# top.net
KiCad netlist of a schematic drawn in Altium Designer
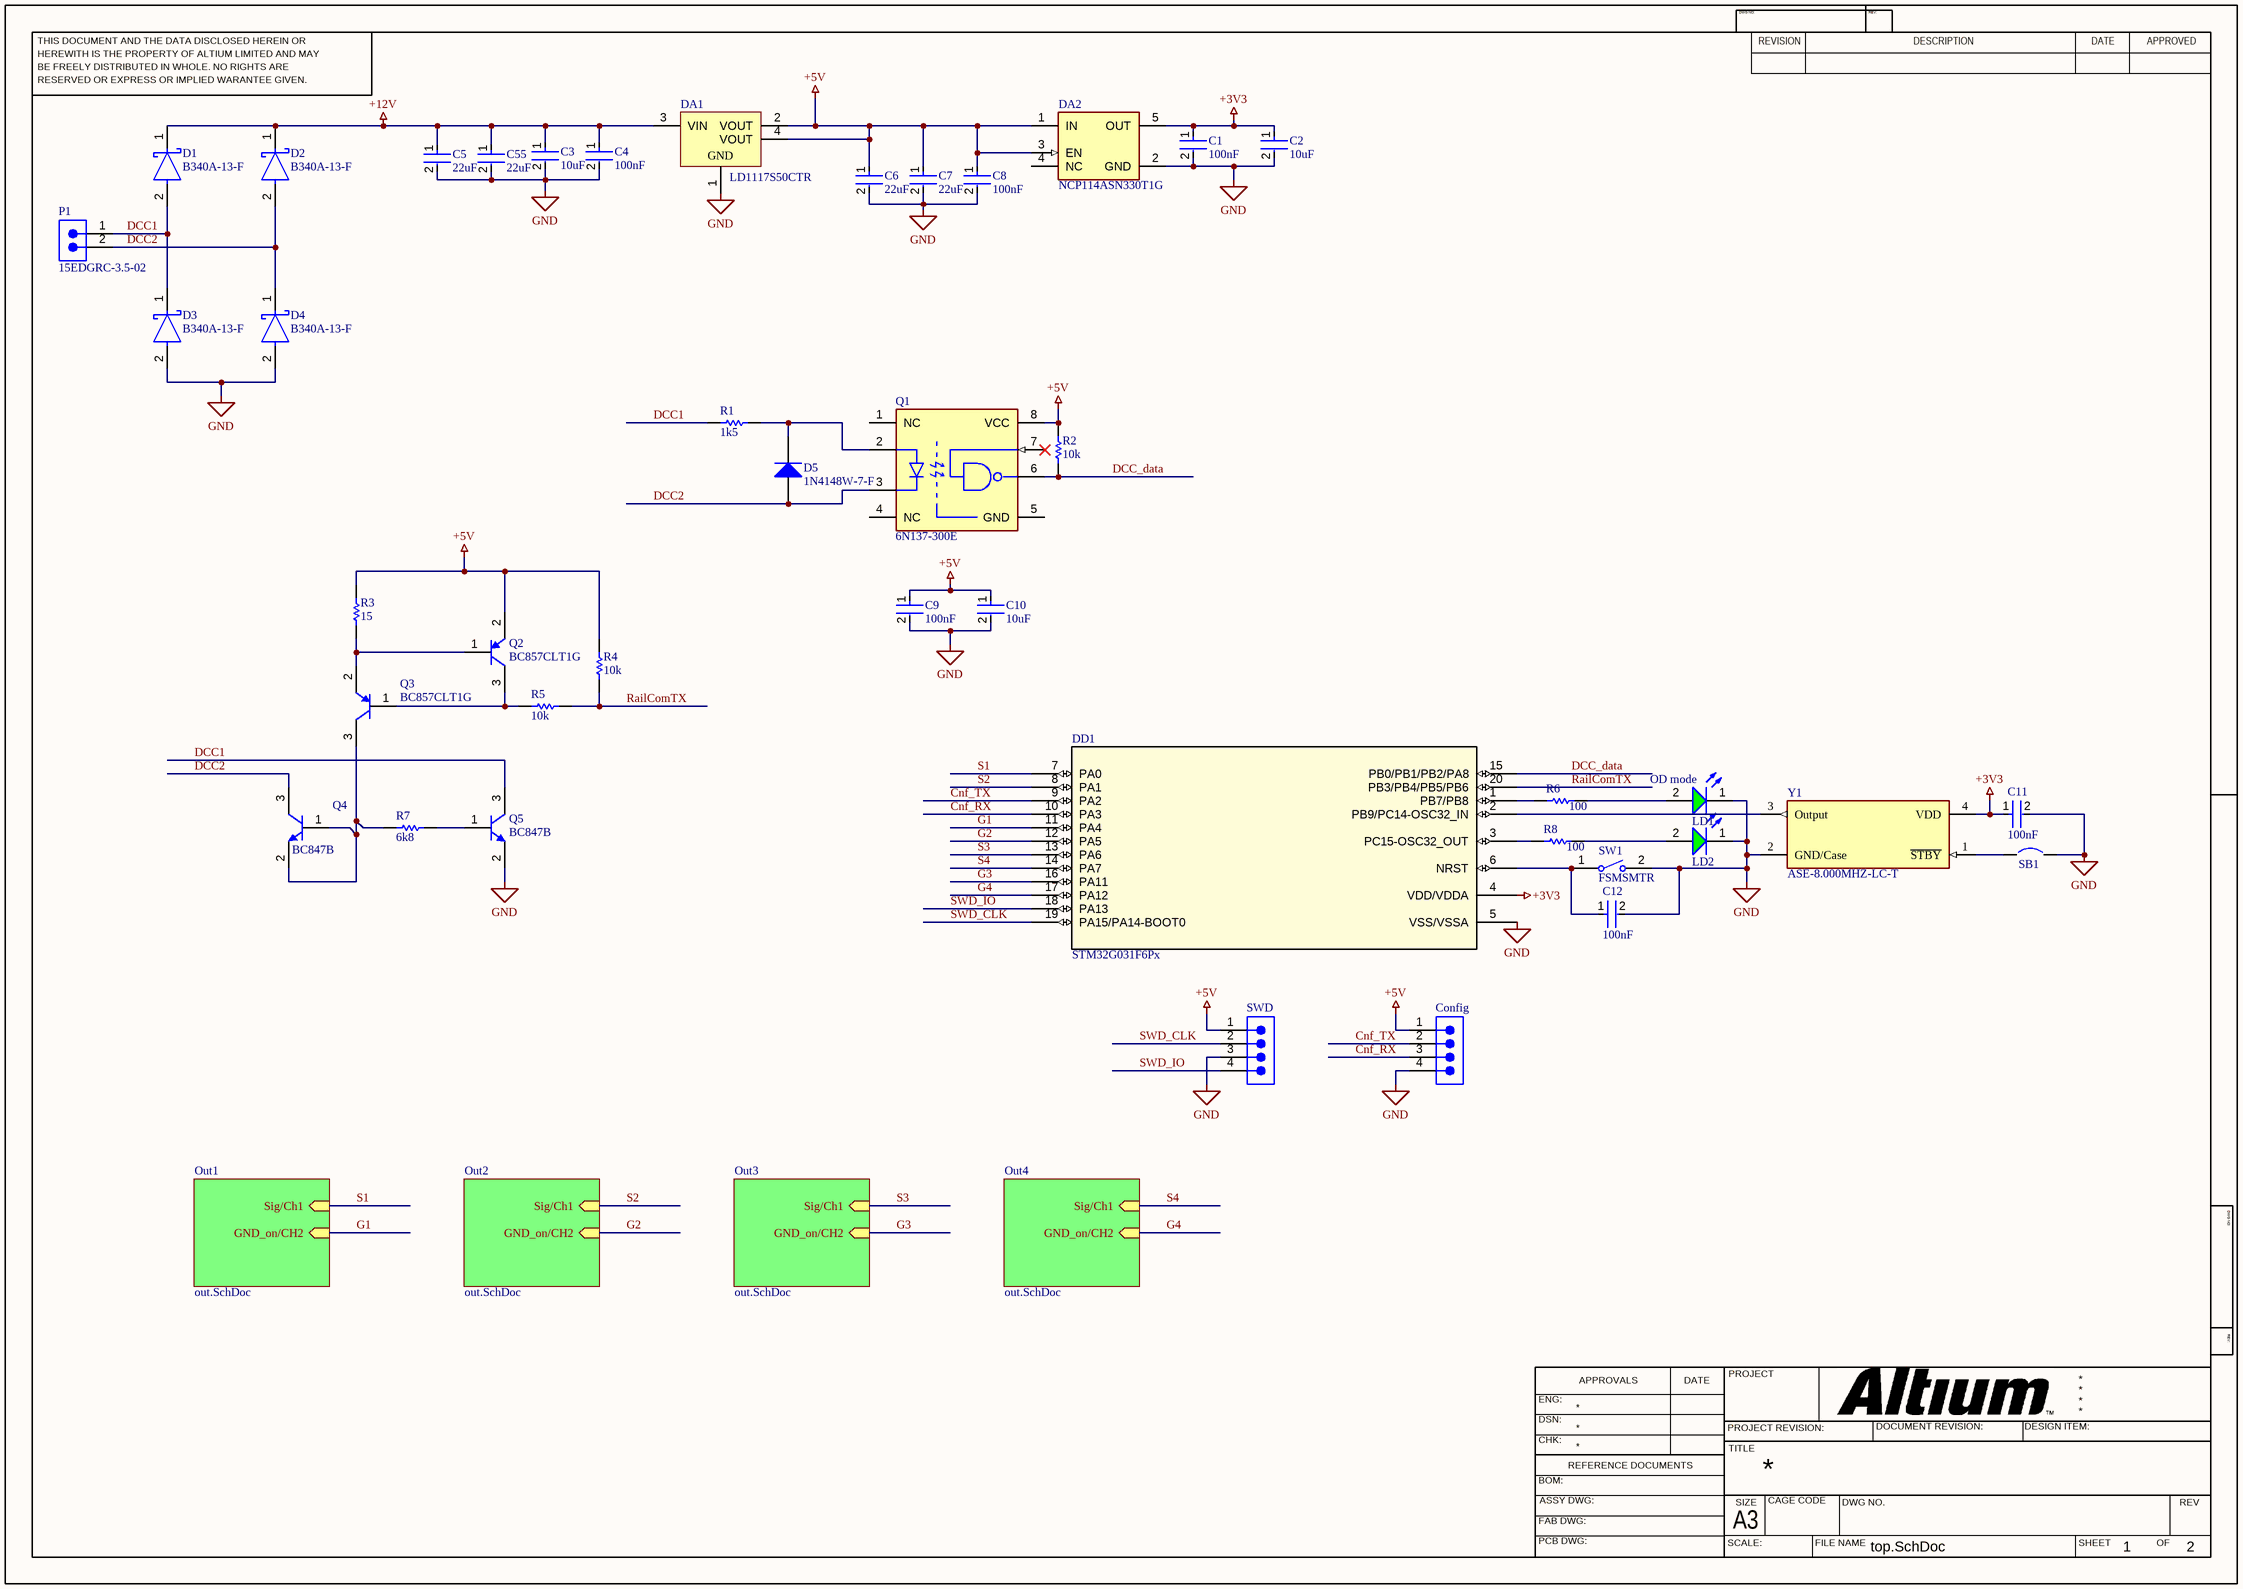
[diagram p0: top.SchDoc]

(export (version "E")
  (design (tool "Eeschema 10.0.6"))
  (components
    (comp (ref "C1")
      (value "CGA3E2X7R1H104K080AA")
      (footprint "FP-CGA3E-0_3-0_1-IPC_C")
      (description "Cap Ceramic 100nF 50V X7R 10% Pad SMD 0603 +125°C Automotive T/R")
      (fields
        (field (name "TOLERANCE") "10%")
        (field (name "CAPACITANCE") "100nF")
        (field (name "VOLTAGE") "50V")
      )
      (libsource (lib "Altium Content Vault") (part "b4654b650e69147ec39a6b967a45e02"))
    )
    (comp (ref "C2")
      (value "GRM188R60J106ME47D")
      (footprint "FP-GRM188-0_1-e0_2_0_55-IPC_C")
      (description "Chip Multilayer Ceramic Capacitors for General Purpose, 0603, 10uF, X5R, 15%, 20%, 6.3V")
      (fields
        (field (name "CAPACITANCE") "10uF")
        (field (name "VOLTAGE") "6.3V")
        (field (name "TOLERANCE") "20%")
      )
      (libsource (lib "Altium Content Vault") (part "02cd4be3c70576c341d710602a673aa"))
    )
    (comp (ref "C3")
      (value "GRM188R60J106ME47D")
      (footprint "FP-GRM188-0_1-e0_2_0_55-IPC_C")
      (description "Chip Multilayer Ceramic Capacitors for General Purpose, 0603, 10uF, X5R, 15%, 20%, 6.3V")
      (fields
        (field (name "CAPACITANCE") "10uF")
        (field (name "VOLTAGE") "6.3V")
        (field (name "TOLERANCE") "20%")
      )
      (libsource (lib "Altium Content Vault") (part "02cd4be3c70576c341d710602a673aa"))
    )
    (comp (ref "C4")
      (value "CGA3E2X7R1H104K080AA")
      (footprint "FP-CGA3E-0_3-0_1-IPC_C")
      (description "Cap Ceramic 100nF 50V X7R 10% Pad SMD 0603 +125°C Automotive T/R")
      (fields
        (field (name "TOLERANCE") "10%")
        (field (name "CAPACITANCE") "100nF")
        (field (name "VOLTAGE") "50V")
      )
      (libsource (lib "Altium Content Vault") (part "b4654b650e69147ec39a6b967a45e02"))
    )
    (comp (ref "C5")
      (value "GRM188R61A226ME15D")
      (footprint "FP-GRM188-0_2-IPC_C")
      (description "Chip Multilayer Ceramic Capacitors for General Purpose, 0603, 22uF, X5R, 15%, 20%, 10V")
      (fields (field (name "TOLERANCE") "20%") (field (name "CAPACITANCE") "22uF"))
      (libsource (lib "Altium Content Vault") (part "11868f565c42a9108669ba33697ecf6"))
    )
    (comp (ref "C6")
      (value "GRM188R61A226ME15D")
      (footprint "FP-GRM188-0_2-IPC_C")
      (description "Chip Multilayer Ceramic Capacitors for General Purpose, 0603, 22uF, X5R, 15%, 20%, 10V")
      (fields (field (name "TOLERANCE") "20%") (field (name "CAPACITANCE") "22uF"))
      (libsource (lib "Altium Content Vault") (part "11868f565c42a9108669ba33697ecf6"))
    )
    (comp (ref "C7")
      (value "GRM188R61A226ME15D")
      (footprint "FP-GRM188-0_2-IPC_C")
      (description "Chip Multilayer Ceramic Capacitors for General Purpose, 0603, 22uF, X5R, 15%, 20%, 10V")
      (fields (field (name "TOLERANCE") "20%") (field (name "CAPACITANCE") "22uF"))
      (libsource (lib "Altium Content Vault") (part "11868f565c42a9108669ba33697ecf6"))
    )
    (comp (ref "C8")
      (value "CGA3E2X7R1H104K080AA")
      (footprint "FP-CGA3E-0_3-0_1-IPC_C")
      (description "Cap Ceramic 100nF 50V X7R 10% Pad SMD 0603 +125°C Automotive T/R")
      (fields
        (field (name "TOLERANCE") "10%")
        (field (name "CAPACITANCE") "100nF")
        (field (name "VOLTAGE") "50V")
      )
      (libsource (lib "Altium Content Vault") (part "b4654b650e69147ec39a6b967a45e02"))
    )
    (comp (ref "C9")
      (value "CGA3E2X7R1H104K080AA")
      (footprint "FP-CGA3E-0_3-0_1-IPC_C")
      (description "Cap Ceramic 100nF 50V X7R 10% Pad SMD 0603 +125°C Automotive T/R")
      (fields
        (field (name "TOLERANCE") "10%")
        (field (name "CAPACITANCE") "100nF")
        (field (name "VOLTAGE") "50V")
      )
      (libsource (lib "Altium Content Vault") (part "b4654b650e69147ec39a6b967a45e02"))
    )
    (comp (ref "C10")
      (value "GRM188R60J106ME47D")
      (footprint "FP-GRM188-0_1-e0_2_0_55-IPC_C")
      (description "Chip Multilayer Ceramic Capacitors for General Purpose, 0603, 10uF, X5R, 15%, 20%, 6.3V")
      (fields
        (field (name "CAPACITANCE") "10uF")
        (field (name "VOLTAGE") "6.3V")
        (field (name "TOLERANCE") "20%")
      )
      (libsource (lib "Altium Content Vault") (part "02cd4be3c70576c341d710602a673aa"))
    )
    (comp (ref "C11")
      (value "CGA3E2X7R1H104K080AA")
      (footprint "FP-CGA3E-0_3-0_1-IPC_C")
      (description "Cap Ceramic 100nF 50V X7R 10% Pad SMD 0603 +125°C Automotive T/R")
      (fields
        (field (name "TOLERANCE") "10%")
        (field (name "CAPACITANCE") "100nF")
        (field (name "VOLTAGE") "50V")
      )
      (libsource (lib "Altium Content Vault") (part "b4654b650e69147ec39a6b967a45e02"))
    )
    (comp (ref "C12")
      (value "CGA3E2X7R1H104K080AA")
      (footprint "FP-CGA3E-0_3-0_1-IPC_C")
      (description "Cap Ceramic 100nF 50V X7R 10% Pad SMD 0603 +125°C Automotive T/R")
      (fields
        (field (name "TOLERANCE") "10%")
        (field (name "CAPACITANCE") "100nF")
        (field (name "VOLTAGE") "50V")
      )
      (libsource (lib "Altium Content Vault") (part "b4654b650e69147ec39a6b967a45e02"))
    )
    (comp (ref "C55")
      (value "GRM188R61A226ME15D")
      (footprint "FP-GRM188-0_2-IPC_C")
      (description "Chip Multilayer Ceramic Capacitors for General Purpose, 0603, 22uF, X5R, 15%, 20%, 10V")
      (fields (field (name "TOLERANCE") "20%") (field (name "CAPACITANCE") "22uF"))
      (libsource (lib "Altium Content Vault") (part "11868f565c42a9108669ba33697ecf6"))
    )
    (comp (ref "Config")
      (value "61300411121")
      (footprint "61300411121")
      (libsource (lib "Altium Content Vault") (part "Header_Male_1R_04P"))
    )
    (comp (ref "D1")
      (value "B340A-13-F")
      (footprint "FP-SMA-MFG")
      (description "DIODE SCHOTTKY 40V 3A SMA")
      (fields (field (name "VOLTAGE") "40V"))
      (libsource (lib "Altium Content Vault") (part "1d6ec82d83fb6aee721767c19dac4b9"))
    )
    (comp (ref "D2")
      (value "B340A-13-F")
      (footprint "FP-SMA-MFG")
      (description "DIODE SCHOTTKY 40V 3A SMA")
      (fields (field (name "VOLTAGE") "40V"))
      (libsource (lib "Altium Content Vault") (part "1d6ec82d83fb6aee721767c19dac4b9"))
    )
    (comp (ref "D3")
      (value "B340A-13-F")
      (footprint "FP-SMA-MFG")
      (description "DIODE SCHOTTKY 40V 3A SMA")
      (fields (field (name "VOLTAGE") "40V"))
      (libsource (lib "Altium Content Vault") (part "1d6ec82d83fb6aee721767c19dac4b9"))
    )
    (comp (ref "D4")
      (value "B340A-13-F")
      (footprint "FP-SMA-MFG")
      (description "DIODE SCHOTTKY 40V 3A SMA")
      (fields (field (name "VOLTAGE") "40V"))
      (libsource (lib "Altium Content Vault") (part "1d6ec82d83fb6aee721767c19dac4b9"))
    )
    (comp (ref "D5")
      (value "1N4148W-7-F")
      (footprint "DIOD-SOD123-2_V")
      (description "Fast Switching Diode, 100 V, 0.15 A, -65 to 150 degC, 2-Pin?SOD123, RoHS, Tape and Reel")
      (fields (field (name "MANUFACTURER") "DiodesIncorporated"))
      (libsource (lib "Altium Content Vault") (part "D-AK-2"))
    )
    (comp (ref "DA1")
      (value "LD1117S50CTR")
      (footprint "SOT-223_N")
      (description "Fixed Low Drop Positive Voltage Regulator, 5V, 4-Pin SOT-223, Tape and Reel")
      (libsource (lib "Altium Content Vault") (part "PM-REG-LD1117-SOT4"))
    )
    (comp (ref "DA2")
      (value "NCP114ASN330T1G")
      (footprint "FP-483-MFG")
      (description "IC REG LINEAR 3.3V 300MA 5TSOP")
      (fields
        (field (name "MANUFACTURER") "ON Semiconductor")
        (field (name "OCTOPART") "https://octopart.com/ncp114asn330t1g-on+semiconductor-74628742")
      )
      (libsource (lib "Altium Content Vault") (part "57814aa37072aacea77ef0fe9350350"))
    )
    (comp (ref "DD1")
      (value "STM32G031F6Px")
      (footprint "TSSOP20")
      (fields
        (field (name "MANUFACTURER_PART_NUMBER") "stm32g0_tssop20_t1")
        (field (name "COPYRIGHT") "Copyright (C) 2018 Accelerated Designs. All rights reserved")
      )
      (libsource (lib "ST Microelectronics STM32 G0") (part "STM32G031F6Px"))
    )
    (comp (ref "LD1")
      (value "150060VS75000")
      (footprint "WL-SMCW_0603_150060xx75000")
      (description "WURTH ELEKTRONIK - 150060VS75000 - LED, Green, SMD, 0603, 30 mA, 2 V, 570 nm")
      (libsource (lib "Altium Content Vault") (part "LED_Green_2A-1K"))
    )
    (comp (ref "LD2")
      (value "150060VS75000")
      (footprint "WL-SMCW_0603_150060xx75000")
      (description "WURTH ELEKTRONIK - 150060VS75000 - LED, Green, SMD, 0603, 30 mA, 2 V, 570 nm")
      (libsource (lib "Altium Content Vault") (part "LED_Green_2A-1K"))
    )
    (comp (ref "P1")
      (value "15EDGRC-3.5-02")
      (footprint "691305140002")
      (libsource (lib "Altium Content Vault") (part "TBL - 1R - 02P - Male"))
    )
    (comp (ref "Q1")
      (value "6N137-300E")
      (footprint "FP-6N137-300E-MFG")
      (description "OPTOISO 3.75KV OPN COLL 8DIP GW")
      (fields
        (field (name "MANUFACTURER") "Broadcom")
        (field (name "OCTOPART") "https://octopart.com/6n137-300e-broadcom-71125550")
      )
      (libsource (lib "Altium Content Vault") (part "086db94909ba3b4bba0ec19532872cc"))
    )
    (comp (ref "Q2")
      (value "BC857CLT1G")
      (footprint "ONSC-SOT-23-3-318-08_V")
      (description "General Purpose Transistor, PNP Silicon, 3-Pin SOT-23, Pb-Free, Tape and Reel")
      (fields (field (name "MANUFACTURER") "On Semiconductor"))
      (libsource (lib "Altium Content Vault") (part "ONSC-PNP-B1E2C3-3"))
    )
    (comp (ref "Q3")
      (value "BC857CLT1G")
      (footprint "ONSC-SOT-23-3-318-08_V")
      (description "General Purpose Transistor, PNP Silicon, 3-Pin SOT-23, Pb-Free, Tape and Reel")
      (fields (field (name "MANUFACTURER") "On Semiconductor"))
      (libsource (lib "Altium Content Vault") (part "ONSC-PNP-B1E2C3-3"))
    )
    (comp (ref "Q4")
      (value "BC847B")
      (footprint "INF-SOT23_M")
      (description "NPN Silicon AF Transistor, 45 V VCEO, 100 mA IC, SOT23, Reel, Green")
      (fields (field (name "MANUFACTURER") "Infineon"))
      (libsource (lib "Altium Content Vault") (part "INF-BJTNPN-BEC-3"))
    )
    (comp (ref "Q5")
      (value "BC847B")
      (footprint "INF-SOT23_M")
      (description "NPN Silicon AF Transistor, 45 V VCEO, 100 mA IC, SOT23, Reel, Green")
      (fields (field (name "MANUFACTURER") "Infineon"))
      (libsource (lib "Altium Content Vault") (part "INF-BJTNPN-BEC-3"))
    )
    (comp (ref "R1")
      (value "1k5")
      (footprint "RESC1608X55X25ML10T15")
      (description "Chip Resistor, 1.5 KOhm, +/- 1%, 0.1 W, -55 to 155 degC, 0603 (1608 Metric), RoHS, Tape and Reel")
      (fields (field (name "TOLERANCE") "1%") (field (name "MANUFACTURER") "Yageo"))
      (libsource (lib "Altium Content Vault") (part "RES-2"))
    )
    (comp (ref "R2")
      (value "10k")
      (footprint "RESC1609X55X30NL15T15")
      (description "Chip Resistor, 10 KOhm, +/- 1%, 0.1 W, -55 to 155 degC, 0603 (1608 Metric), RoHS, Tape and Reel")
      (fields (field (name "TOLERANCE") "1%") (field (name "MANUFACTURER") "Panasonic"))
      (libsource (lib "Altium Content Vault") (part "RES-2"))
    )
    (comp (ref "R3")
      (value "15")
      (footprint "RESC1608X55X30NL15T15")
      (fields (field (name "PART NUMBER") "ERJ-3EKF1502V") (field (name "MANUFACTURER") "Panasonic"))
      (libsource (lib "Altium Content Vault") (part "RES"))
    )
    (comp (ref "R4")
      (value "10k")
      (footprint "RESC1609X55X30NL15T15")
      (description "Chip Resistor, 10 KOhm, +/- 1%, 0.1 W, -55 to 155 degC, 0603 (1608 Metric), RoHS, Tape and Reel")
      (fields (field (name "TOLERANCE") "1%") (field (name "MANUFACTURER") "Panasonic"))
      (libsource (lib "Altium Content Vault") (part "RES-2"))
    )
    (comp (ref "R5")
      (value "10k")
      (footprint "RESC1609X55X30NL15T15")
      (description "Chip Resistor, 10 KOhm, +/- 1%, 0.1 W, -55 to 155 degC, 0603 (1608 Metric), RoHS, Tape and Reel")
      (fields (field (name "TOLERANCE") "1%") (field (name "MANUFACTURER") "Panasonic"))
      (libsource (lib "Altium Content Vault") (part "RES-2"))
    )
    (comp (ref "R6")
      (value "100")
      (footprint "RESC1608X55X30NL15T15")
      (fields (field (name "PART NUMBER") "ERJ-3EKF1003V") (field (name "MANUFACTURER") "Panasonic"))
      (libsource (lib "Altium Content Vault") (part "RES"))
    )
    (comp (ref "R7")
      (value "6k8")
      (footprint "RESC1608X55X25NL10T15")
      (description "Chip Resistor, 6.8 KOhm, +/- 1%, 100 mW, -55 to 155 degC, 0603 (1608 Metric), RoHS, Tape and Reel")
      (fields (field (name "Comment") "RC0603FR-076K8L"))
      (libsource (lib "Altium Content Vault") (part "RES-2"))
    )
    (comp (ref "R8")
      (value "100")
      (footprint "RESC1608X55X30NL15T15")
      (fields (field (name "PART NUMBER") "ERJ-3EKF1003V") (field (name "MANUFACTURER") "Panasonic"))
      (libsource (lib "Altium Content Vault") (part "RES"))
    )
    (comp (ref "SB1")
      (value "~")
      (footprint "JP_SMD")
      (description "Circuit Breaker")
      (fields (field (name "PUBLISHER") "Altium Limited"))
      (libsource (lib "test_adc") (part "Circuit Breaker"))
    )
    (comp (ref "SW1")
      (value "FSMSMTR")
      (footprint "TECO-FSMSMTR_V")
      (description "FSMSM Push Button Switch, 50 mA, -35 to 85 degC, 2-Pin SMD, RoHS, Tape and Reel")
      (fields (field (name "MANUFACTURER") "TE Connectivity"))
      (libsource (lib "Altium Content Vault") (part "SW-SPST-2_C"))
    )
    (comp (ref "SWD")
      (value "61300411121")
      (footprint "61300411121")
      (libsource (lib "Altium Content Vault") (part "Header_Male_1R_04P"))
    )
    (comp (ref "Y1")
      (value "ASE-8.000MHZ-LC-T")
      (footprint "FP-ASE-MFG")
      (description "XTAL Oscillator 8MHz ±50ppm CMOS 3.3V 4-SMD 3.2mm x 2.5mm")
      (libsource (lib "Altium Content Vault") (part "61a724e6190563596ac712fef61ad37"))
    )
  )
  (nets
    (net (code "1") (name "+3V3") (class "Default")
      (node (ref "C1") (pin "1") (pinfunction "1_1") (pintype "passive"))
      (node (ref "C11") (pin "1") (pinfunction "1_1") (pintype "passive"))
      (node (ref "C2") (pin "1") (pinfunction "1_1") (pintype "passive"))
      (node (ref "DA2") (pin "5") (pinfunction "OUT_5") (pintype "power_in"))
      (node (ref "DD1") (pin "4") (pinfunction "VDD/VDDA_4") (pintype "power_in"))
      (node (ref "Y1") (pin "4") (pinfunction "VDD_4") (pintype "power_in"))
    )
    (net (code "2") (name "+5V") (class "Default")
      (node (ref "C10") (pin "1") (pinfunction "1_1") (pintype "passive"))
      (node (ref "C6") (pin "1") (pinfunction "1_1") (pintype "passive"))
      (node (ref "C7") (pin "1") (pinfunction "1_1") (pintype "passive"))
      (node (ref "C8") (pin "1") (pinfunction "1_1") (pintype "passive"))
      (node (ref "C9") (pin "1") (pinfunction "1_1") (pintype "passive"))
      (node (ref "Config") (pin "1") (pinfunction "1_1") (pintype "passive"))
      (node (ref "DA1") (pin "2") (pinfunction "VOUT_2") (pintype "power_in"))
      (node (ref "DA1") (pin "4") (pinfunction "VOUT_4") (pintype "power_in"))
      (node (ref "DA2") (pin "1") (pinfunction "IN_1") (pintype "power_in"))
      (node (ref "DA2") (pin "3") (pinfunction "EN_3") (pintype "input"))
      (node (ref "Q1") (pin "8") (pinfunction "VCC_8") (pintype "power_in"))
      (node (ref "Q2") (pin "2") (pinfunction "E_2") (pintype "passive"))
      (node (ref "R2") (pin "1") (pinfunction "1_1") (pintype "passive"))
      (node (ref "R3") (pin "2") (pinfunction "2_2") (pintype "passive"))
      (node (ref "R4") (pin "1") (pinfunction "1_1") (pintype "passive"))
      (node (ref "SWD") (pin "1") (pinfunction "1_1") (pintype "passive"))
    )
    (net (code "3") (name "+12V") (class "Default")
      (node (ref "C3") (pin "1") (pinfunction "1_1") (pintype "passive"))
      (node (ref "C4") (pin "1") (pinfunction "1_1") (pintype "passive"))
      (node (ref "C5") (pin "1") (pinfunction "1_1") (pintype "passive"))
      (node (ref "C55") (pin "1") (pinfunction "1_1") (pintype "passive"))
      (node (ref "D1") (pin "1") (pinfunction "C_1") (pintype "passive"))
      (node (ref "D2") (pin "1") (pinfunction "C_1") (pintype "passive"))
      (node (ref "DA1") (pin "3") (pinfunction "VIN_3") (pintype "power_in"))
    )
    (net (code "4") (name "/Cnf_RX") (class "Default")
      (node (ref "Config") (pin "3") (pinfunction "3_3") (pintype "passive"))
      (node (ref "DD1") (pin "10") (pinfunction "PA3_10") (pintype "bidirectional"))
    )
    (net (code "5") (name "/Cnf_TX") (class "Default")
      (node (ref "Config") (pin "2") (pinfunction "2_2") (pintype "passive"))
      (node (ref "DD1") (pin "9") (pinfunction "PA2_9") (pintype "bidirectional"))
    )
    (net (code "6") (name "/DCC1") (class "Default")
      (node (ref "D1") (pin "2") (pinfunction "A_2") (pintype "passive"))
      (node (ref "D3") (pin "1") (pinfunction "C_1") (pintype "passive"))
      (node (ref "P1") (pin "1") (pinfunction "1_1") (pintype "passive"))
      (node (ref "Q5") (pin "3") (pinfunction "C_3") (pintype "passive"))
      (node (ref "R1") (pin "1") (pinfunction "1_1") (pintype "passive"))
    )
    (net (code "7") (name "/DCC2") (class "Default")
      (node (ref "D2") (pin "2") (pinfunction "A_2") (pintype "passive"))
      (node (ref "D4") (pin "1") (pinfunction "C_1") (pintype "passive"))
      (node (ref "D5") (pin "1") (pinfunction "A_1") (pintype "passive"))
      (node (ref "P1") (pin "2") (pinfunction "2_2") (pintype "passive"))
      (node (ref "Q1") (pin "3") (pinfunction "C_3") (pintype "passive"))
      (node (ref "Q4") (pin "3") (pinfunction "C_3") (pintype "passive"))
    )
    (net (code "8") (name "/DCC_data") (class "Default")
      (node (ref "DD1") (pin "15") (pinfunction "PB0/PB1/PB2/PA8_15") (pintype "bidirectional"))
      (node (ref "Q1") (pin "6") (pinfunction "VO_6") (pintype "open_collector"))
      (node (ref "R2") (pin "2") (pinfunction "2_2") (pintype "passive"))
    )
    (net (code "9") (name "/G1") (class "Default")
      (node (ref "DD1") (pin "11") (pinfunction "PA4_11") (pintype "bidirectional"))
    )
    (net (code "10") (name "/G2") (class "Default")
      (node (ref "DD1") (pin "12") (pinfunction "PA5_12") (pintype "bidirectional"))
    )
    (net (code "11") (name "/G3") (class "Default")
      (node (ref "DD1") (pin "16") (pinfunction "PA11_16") (pintype "bidirectional"))
    )
    (net (code "12") (name "/G4") (class "Default")
      (node (ref "DD1") (pin "17") (pinfunction "PA12_17") (pintype "bidirectional"))
    )
    (net (code "13") (name "/RailComTX") (class "Default")
      (node (ref "DD1") (pin "20") (pinfunction "PB3/PB4/PB5/PB6_20") (pintype "bidirectional"))
      (node (ref "R4") (pin "2") (pinfunction "2_2") (pintype "passive"))
      (node (ref "R5") (pin "1") (pinfunction "1_1") (pintype "passive"))
    )
    (net (code "14") (name "/S1") (class "Default")
      (node (ref "DD1") (pin "7") (pinfunction "PA0_7") (pintype "bidirectional"))
    )
    (net (code "15") (name "/S2") (class "Default")
      (node (ref "DD1") (pin "8") (pinfunction "PA1_8") (pintype "bidirectional"))
    )
    (net (code "16") (name "/S3") (class "Default")
      (node (ref "DD1") (pin "13") (pinfunction "PA6_13") (pintype "bidirectional"))
    )
    (net (code "17") (name "/S4") (class "Default")
      (node (ref "DD1") (pin "14") (pinfunction "PA7_14") (pintype "bidirectional"))
    )
    (net (code "18") (name "/SWD_CLK") (class "Default")
      (node (ref "DD1") (pin "19") (pinfunction "PA15/PA14-BOOT0_19") (pintype "bidirectional"))
      (node (ref "SWD") (pin "2") (pinfunction "2_2") (pintype "passive"))
    )
    (net (code "19") (name "/SWD_IO") (class "Default")
      (node (ref "DD1") (pin "18") (pinfunction "PA13_18") (pintype "bidirectional"))
      (node (ref "SWD") (pin "4") (pinfunction "4_4") (pintype "passive"))
    )
    (net (code "20") (name "GND") (class "Default")
      (node (ref "C1") (pin "2") (pinfunction "2_2") (pintype "passive"))
      (node (ref "C10") (pin "2") (pinfunction "2_2") (pintype "passive"))
      (node (ref "C11") (pin "2") (pinfunction "2_2") (pintype "passive"))
      (node (ref "C12") (pin "2") (pinfunction "2_2") (pintype "passive"))
      (node (ref "C2") (pin "2") (pinfunction "2_2") (pintype "passive"))
      (node (ref "C3") (pin "2") (pinfunction "2_2") (pintype "passive"))
      (node (ref "C4") (pin "2") (pinfunction "2_2") (pintype "passive"))
      (node (ref "C5") (pin "2") (pinfunction "2_2") (pintype "passive"))
      (node (ref "C55") (pin "2") (pinfunction "2_2") (pintype "passive"))
      (node (ref "C6") (pin "2") (pinfunction "2_2") (pintype "passive"))
      (node (ref "C7") (pin "2") (pinfunction "2_2") (pintype "passive"))
      (node (ref "C8") (pin "2") (pinfunction "2_2") (pintype "passive"))
      (node (ref "C9") (pin "2") (pinfunction "2_2") (pintype "passive"))
      (node (ref "Config") (pin "4") (pinfunction "4_4") (pintype "passive"))
      (node (ref "D3") (pin "2") (pinfunction "A_2") (pintype "passive"))
      (node (ref "D4") (pin "2") (pinfunction "A_2") (pintype "passive"))
      (node (ref "DA1") (pin "1") (pinfunction "GND_1") (pintype "power_in"))
      (node (ref "DA2") (pin "2") (pinfunction "GND_2") (pintype "power_in"))
      (node (ref "DD1") (pin "5") (pinfunction "VSS/VSSA_5") (pintype "power_in"))
      (node (ref "LD1") (pin "1") (pinfunction "K_1") (pintype "passive"))
      (node (ref "LD2") (pin "1") (pinfunction "K_1") (pintype "passive"))
      (node (ref "Q5") (pin "2") (pinfunction "E_2") (pintype "passive"))
      (node (ref "SB1") (pin "2") (pinfunction "2_2") (pintype "passive"))
      (node (ref "SW1") (pin "2") (pinfunction "2_2") (pintype "passive"))
      (node (ref "SWD") (pin "3") (pinfunction "3_3") (pintype "passive"))
      (node (ref "Y1") (pin "2") (pinfunction "GND/Case_2") (pintype "power_in"))
    )
    (net (code "21") (name "Net-(D5-K)") (class "Default")
      (node (ref "D5") (pin "2") (pinfunction "K_2") (pintype "passive"))
      (node (ref "Q1") (pin "2") (pinfunction "A_2") (pintype "passive"))
      (node (ref "R1") (pin "2") (pinfunction "2_2") (pintype "passive"))
    )
    (net (code "22") (name "Net-(DD1-NRST)") (class "Default")
      (node (ref "C12") (pin "1") (pinfunction "1_1") (pintype "passive"))
      (node (ref "DD1") (pin "6") (pinfunction "NRST_6") (pintype "bidirectional"))
      (node (ref "SW1") (pin "1") (pinfunction "1_1") (pintype "passive"))
    )
    (net (code "23") (name "Net-(DD1-PB7{slash}PB8)") (class "Default")
      (node (ref "DD1") (pin "1") (pinfunction "PB7/PB8_1") (pintype "bidirectional"))
      (node (ref "R6") (pin "1") (pinfunction "1_1") (pintype "passive"))
    )
    (net (code "24") (name "Net-(DD1-PB9{slash}PC14-OSC32_IN)") (class "Default")
      (node (ref "DD1") (pin "2") (pinfunction "PB9/PC14-OSC32_IN_2") (pintype "bidirectional"))
      (node (ref "Y1") (pin "3") (pinfunction "Output_3") (pintype "output"))
    )
    (net (code "25") (name "Net-(DD1-PC15-OSC32_OUT)") (class "Default")
      (node (ref "DD1") (pin "3") (pinfunction "PC15-OSC32_OUT_3") (pintype "bidirectional"))
      (node (ref "R8") (pin "1") (pinfunction "1_1") (pintype "passive"))
    )
    (net (code "26") (name "Net-(LD1-A)") (class "Default")
      (node (ref "LD1") (pin "2") (pinfunction "A_2") (pintype "passive"))
      (node (ref "R6") (pin "2") (pinfunction "2_2") (pintype "passive"))
    )
    (net (code "27") (name "Net-(LD2-A)") (class "Default")
      (node (ref "LD2") (pin "2") (pinfunction "A_2") (pintype "passive"))
      (node (ref "R8") (pin "2") (pinfunction "2_2") (pintype "passive"))
    )
    (net (code "28") (name "Net-(Q2-B)") (class "Default")
      (node (ref "Q2") (pin "1") (pinfunction "B_1") (pintype "passive"))
      (node (ref "Q3") (pin "2") (pinfunction "E_2") (pintype "passive"))
      (node (ref "R3") (pin "1") (pinfunction "1_1") (pintype "passive"))
    )
    (net (code "29") (name "Net-(Q2-C)") (class "Default")
      (node (ref "Q2") (pin "3") (pinfunction "C_3") (pintype "passive"))
      (node (ref "Q3") (pin "1") (pinfunction "B_1") (pintype "passive"))
      (node (ref "R5") (pin "2") (pinfunction "2_2") (pintype "passive"))
    )
    (net (code "30") (name "Net-(Q3-C)") (class "Default")
      (node (ref "Q3") (pin "3") (pinfunction "C_3") (pintype "passive"))
      (node (ref "Q4") (pin "1") (pinfunction "B_1") (pintype "passive"))
      (node (ref "Q4") (pin "2") (pinfunction "E_2") (pintype "passive"))
      (node (ref "R7") (pin "1") (pinfunction "1_1") (pintype "passive"))
    )
    (net (code "31") (name "Net-(Q5-B)") (class "Default")
      (node (ref "Q5") (pin "1") (pinfunction "B_1") (pintype "passive"))
      (node (ref "R7") (pin "2") (pinfunction "2_2") (pintype "passive"))
    )
    (net (code "32") (name "Net-(Y1-~{STBY})") (class "Default")
      (node (ref "SB1") (pin "1") (pinfunction "1_1") (pintype "passive"))
      (node (ref "Y1") (pin "1") (pinfunction "~{STBY}_1") (pintype "input"))
    )
    (net (code "33") (name "unconnected-(DA2-NC-Pad4)") (class "Default")
      (node (ref "DA2") (pin "4") (pinfunction "NC_4") (pintype "passive"))
    )
    (net (code "34") (name "unconnected-(Q1-GND-Pad5)") (class "Default")
      (node (ref "Q1") (pin "5") (pinfunction "GND_5") (pintype "power_in"))
    )
    (net (code "35") (name "unconnected-(Q1-NC-Pad1)") (class "Default")
      (node (ref "Q1") (pin "1") (pinfunction "NC_1") (pintype "passive"))
    )
    (net (code "36") (name "unconnected-(Q1-NC-Pad4)") (class "Default")
      (node (ref "Q1") (pin "4") (pinfunction "NC_4") (pintype "passive"))
    )
    (net (code "37") (name "unconnected-(Q1-VE-Pad7)") (class "Default")
      (node (ref "Q1") (pin "7") (pinfunction "VE_7") (pintype "input+no_connect"))
    )
  )
)
